# Rear_right_lamp.net
KiCad netlist of a schematic drawn in EAGLE
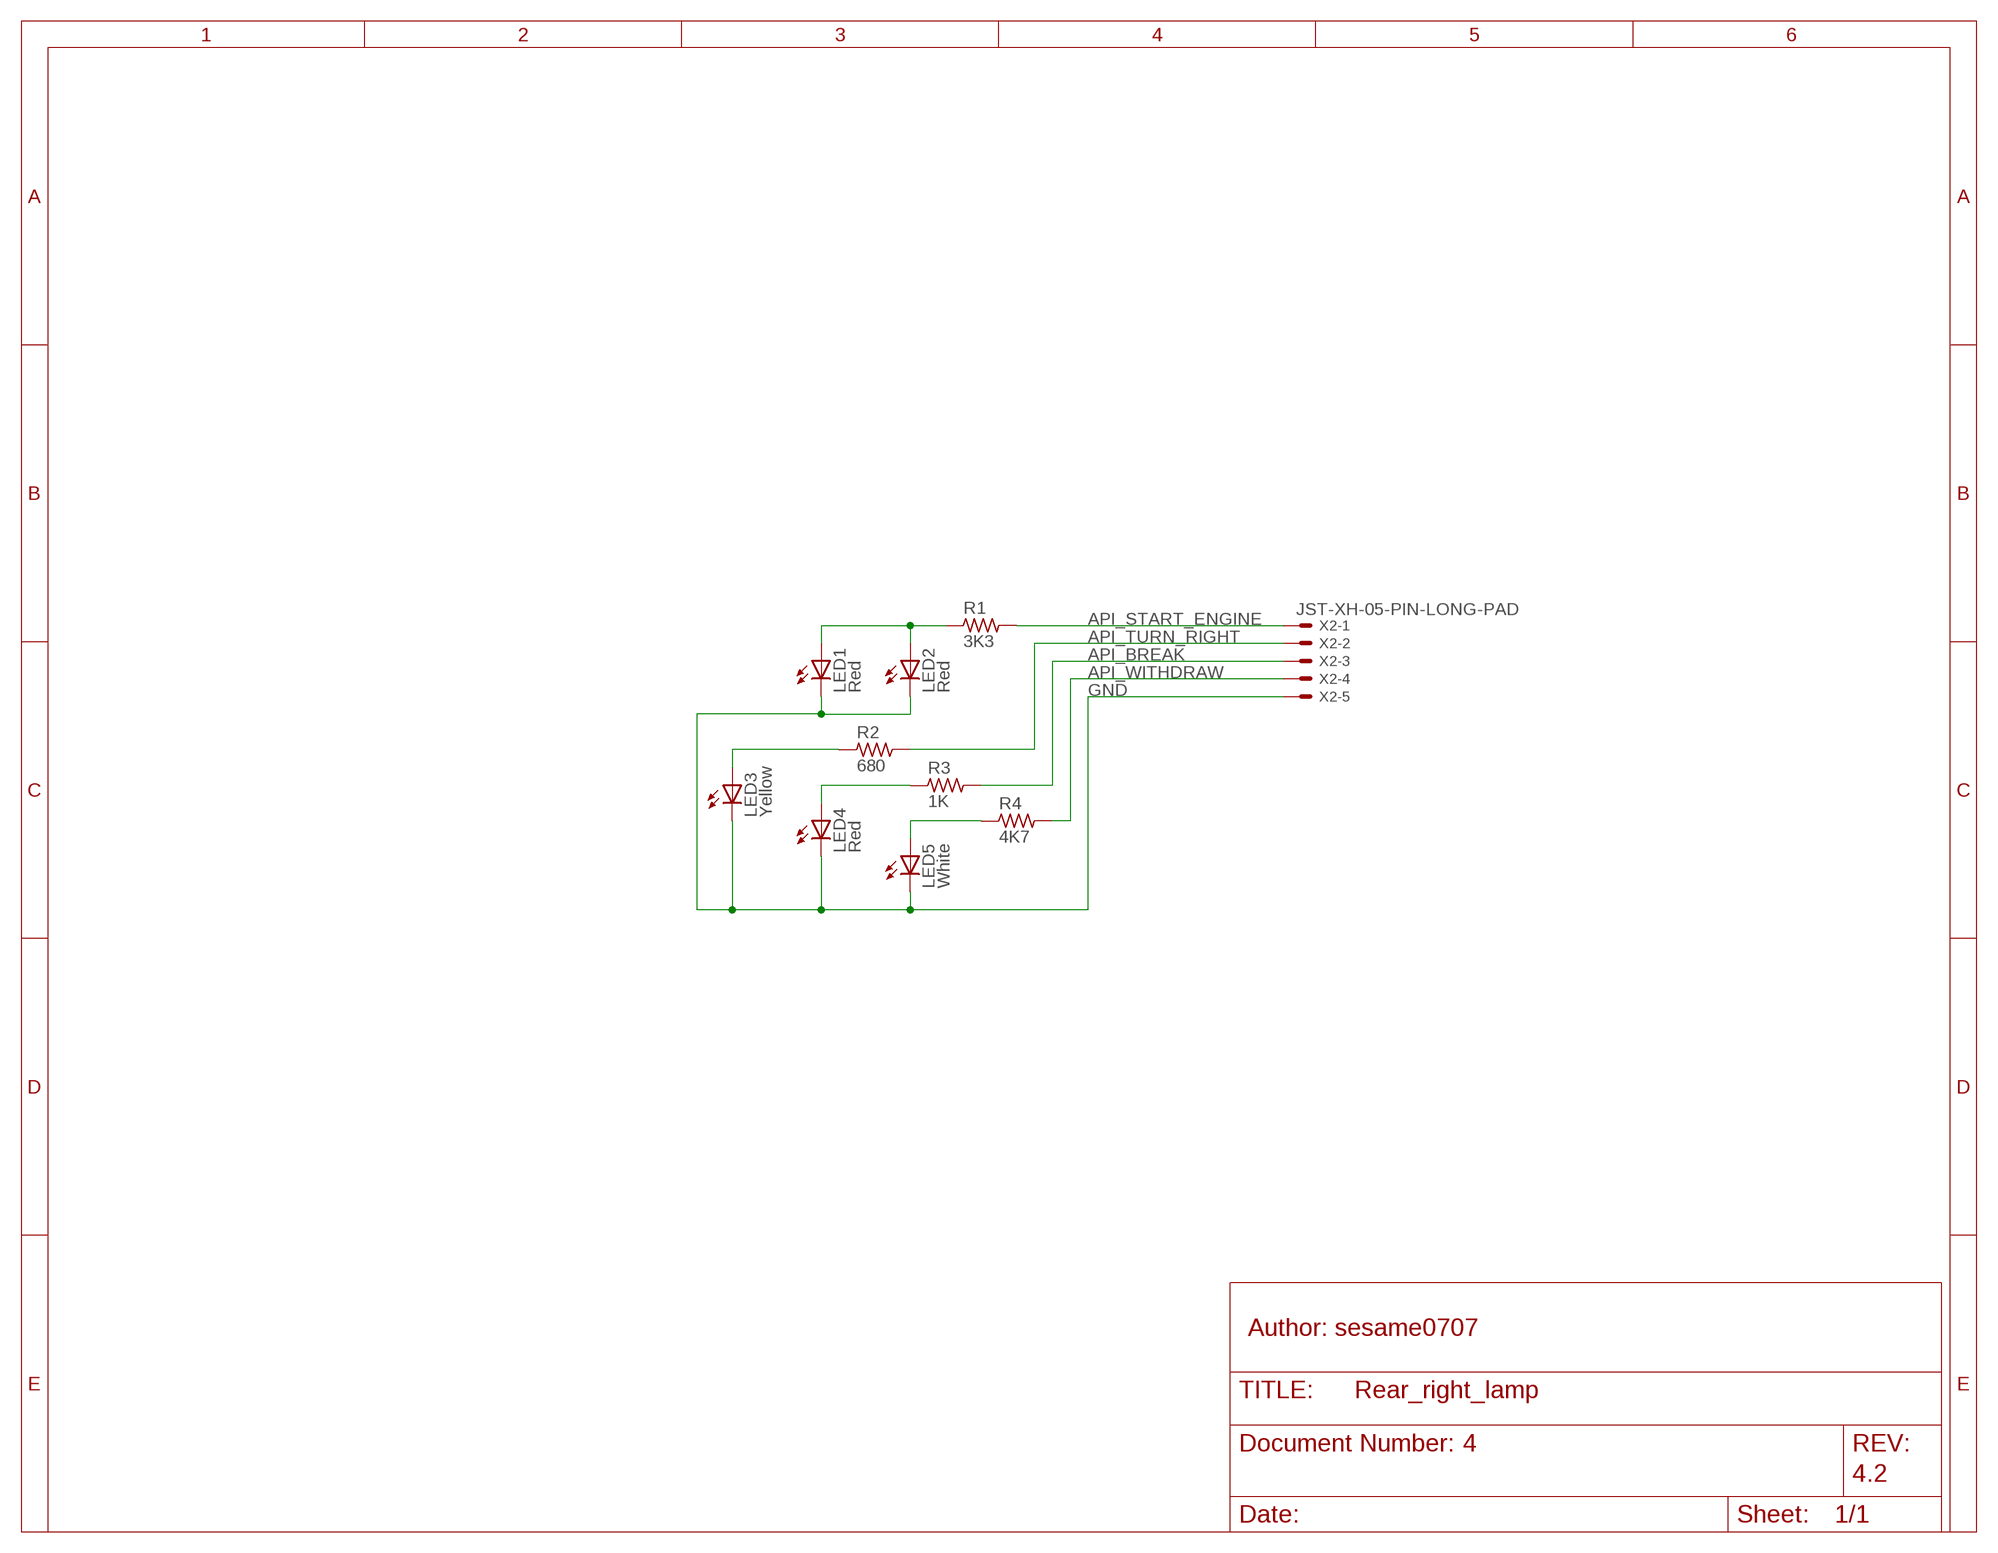
[diagram p0: schematic, sheet 1]

(export (version "E")
  (design (tool "Eeschema 10.0.6"))
  (components
    (comp (ref "LED1")
      (value "Red")
      (footprint "eagle-import:LED5MM")
      (fields
        (field (name "MANUFACTURER") "LUCKYLIGHT")
        (field (name "MANUFACTURER_PART_NUMBER") "LL-503VD2E-1B")
      )
      (libsource (lib "eagle-import") (part "LED5MM"))
    )
    (comp (ref "LED2")
      (value "Red")
      (footprint "eagle-import:LED5MM")
      (fields
        (field (name "MANUFACTURER") "LUCKYLIGHT")
        (field (name "MANUFACTURER_PART_NUMBER") "LL-503VD2E-1B")
      )
      (libsource (lib "eagle-import") (part "LED5MM"))
    )
    (comp (ref "LED3")
      (value "Yellow")
      (footprint "eagle-import:LED5MM")
      (fields
        (field (name "MANUFACTURER") "LUCKYLIGHT")
        (field (name "MANUFACTURER_PART_NUMBER") "LL-503YD2E-1B")
      )
      (libsource (lib "eagle-import") (part "LED5MM"))
    )
    (comp (ref "LED4")
      (value "Red")
      (footprint "eagle-import:LED5MM")
      (fields
        (field (name "MANUFACTURER") "LUCKYLIGHT")
        (field (name "MANUFACTURER_PART_NUMBER") "LL-503VD2E-1B")
      )
      (libsource (lib "eagle-import") (part "LED5MM"))
    )
    (comp (ref "LED5")
      (value "White")
      (footprint "eagle-import:LED5MM")
      (fields
        (field (name "MANUFACTURER") "LUCKYLIGHT")
        (field (name "MANUFACTURER_PART_NUMBER") "LL-504WC2V-W2-3PD")
      )
      (libsource (lib "eagle-import") (part "LED5MM"))
    )
    (comp (ref "R1")
      (value "3K3")
      (footprint "eagle-import:R1206")
      (fields
        (field (name "MANUFACTURER") "ROYAL OHM")
        (field (name "MANUFACTURER_PART_NUMBER") "1206S4J0332T5E")
      )
      (libsource (lib "eagle-import") (part "R_1206"))
    )
    (comp (ref "R2")
      (value "680")
      (footprint "eagle-import:R1206")
      (fields
        (field (name "MANUFACTURER") "ROYAL OHM")
        (field (name "MANUFACTURER_PART_NUMBER") "1206S4J0681T5E")
      )
      (libsource (lib "eagle-import") (part "R_1206"))
    )
    (comp (ref "R3")
      (value "1K")
      (footprint "eagle-import:R1206")
      (fields
        (field (name "MANUFACTURER") "ROYAL OHM")
        (field (name "MANUFACTURER_PART_NUMBER") "1206S4J0102T5E")
      )
      (libsource (lib "eagle-import") (part "R_1206"))
    )
    (comp (ref "R4")
      (value "4K7")
      (footprint "eagle-import:R1206")
      (fields
        (field (name "MANUFACTURER") "ROYAL OHM")
        (field (name "MANUFACTURER_PART_NUMBER") "1206S4J0472T5E")
      )
      (libsource (lib "eagle-import") (part "R_1206"))
    )
    (comp (ref "X2")
      (value "JST-XH-05-PIN-LONG-PAD")
      (footprint "eagle-import:JST-XH-05-PACKAGE-LONG-PAD")
      (libsource (lib "eagle-import") (part "JST-XH-05-PIN-LONG-PAD"))
    )
  )
  (nets
    (net (code "1") (name "/API_BREAK") (class "Default")
      (node (ref "R3") (pin "2") (pinfunction "2_2") (pintype "passive"))
      (node (ref "X2") (pin "3") (pinfunction "S_3") (pintype "passive"))
    )
    (net (code "2") (name "/API_START_ENGINE") (class "Default")
      (node (ref "LED1") (pin "A") (pinfunction "A_A") (pintype "passive"))
      (node (ref "LED2") (pin "A") (pinfunction "A_A") (pintype "passive"))
      (node (ref "R1") (pin "1") (pinfunction "1_1") (pintype "passive"))
    )
    (net (code "3") (name "/API_TURN_RIGHT") (class "Default")
      (node (ref "R2") (pin "2") (pinfunction "2_2") (pintype "passive"))
      (node (ref "X2") (pin "2") (pinfunction "S_2") (pintype "passive"))
    )
    (net (code "4") (name "/API_WITHDRAW") (class "Default")
      (node (ref "R4") (pin "2") (pinfunction "2_2") (pintype "passive"))
      (node (ref "X2") (pin "4") (pinfunction "S_4") (pintype "passive"))
    )
    (net (code "5") (name "/GND") (class "Default")
      (node (ref "LED1") (pin "K") (pinfunction "C_K") (pintype "passive"))
      (node (ref "LED2") (pin "K") (pinfunction "C_K") (pintype "passive"))
      (node (ref "LED3") (pin "K") (pinfunction "C_K") (pintype "passive"))
      (node (ref "LED4") (pin "K") (pinfunction "C_K") (pintype "passive"))
      (node (ref "LED5") (pin "K") (pinfunction "C_K") (pintype "passive"))
      (node (ref "X2") (pin "5") (pinfunction "S_5") (pintype "passive"))
    )
    (net (code "6") (name "Net-(LED3-PadA)") (class "Default")
      (node (ref "LED3") (pin "A") (pinfunction "A_A") (pintype "passive"))
      (node (ref "R2") (pin "1") (pinfunction "1_1") (pintype "passive"))
    )
    (net (code "7") (name "Net-(LED4-PadA)") (class "Default")
      (node (ref "LED4") (pin "A") (pinfunction "A_A") (pintype "passive"))
      (node (ref "R3") (pin "1") (pinfunction "1_1") (pintype "passive"))
    )
    (net (code "8") (name "Net-(LED5-PadA)") (class "Default")
      (node (ref "LED5") (pin "A") (pinfunction "A_A") (pintype "passive"))
      (node (ref "R4") (pin "1") (pinfunction "1_1") (pintype "passive"))
    )
    (net (code "9") (name "Net-(X2A-S)") (class "Default")
      (node (ref "R1") (pin "2") (pinfunction "2_2") (pintype "passive"))
      (node (ref "X2") (pin "1") (pinfunction "S_1") (pintype "passive"))
    )
  )
)
